# 8161930_003__3___2.net
KiCad netlist of a schematic drawn in Altium Designer
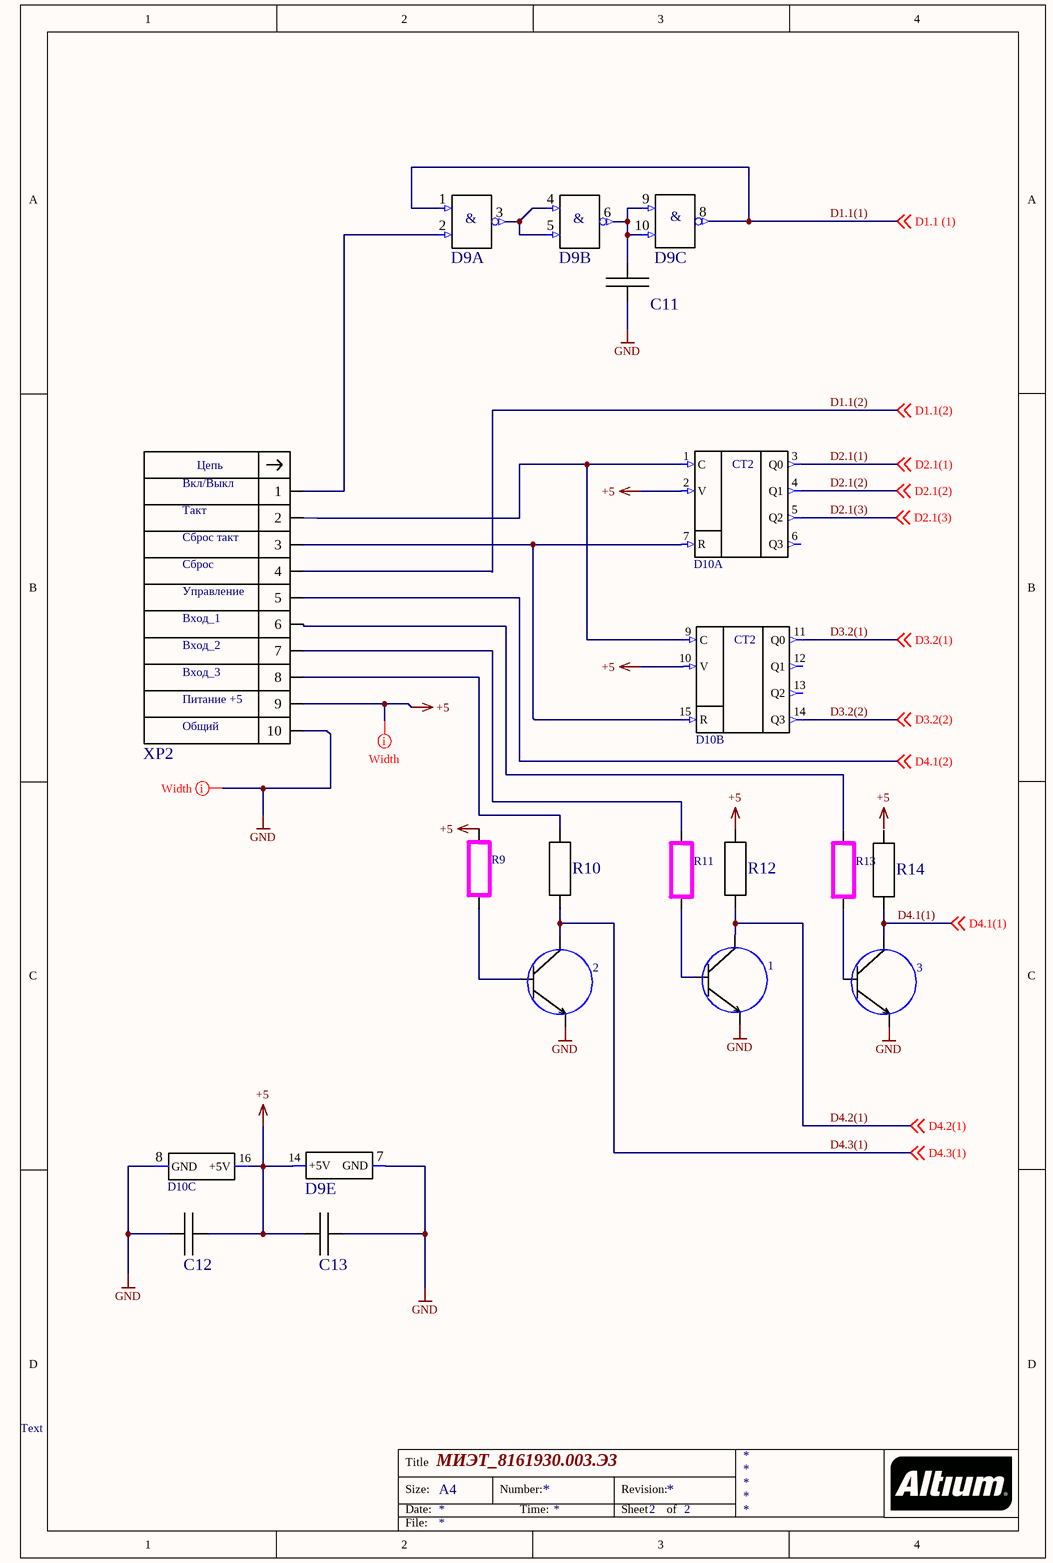
[diagram p0: МИЭТ_8161930_003_Э3_Лист_2.SchDoc]

(export (version "E")
  (design (tool "Eeschema 10.0.6"))
  (components
    (comp (ref "1")
      (value "Транзистор")
      (footprint "Schlib1:SOT89-150P340X160-3N")
      (description "Транзистор 2Т665А9 АЕЯР.432140.605 ТУ")
      (libsource (lib "Schlib1") (part "Транзистор"))
    )
    (comp (ref "2")
      (value "Транзистор")
      (footprint "Schlib1:SOT89-150P340X160-3N")
      (description "Транзистор 2Т665А9 АЕЯР.432140.605 ТУ")
      (libsource (lib "Schlib1") (part "Транзистор"))
    )
    (comp (ref "3")
      (value "Транзистор")
      (footprint "Schlib1:SOT89-150P340X160-3N")
      (description "Транзистор 2Т665А9 АЕЯР.432140.605 ТУ")
      (libsource (lib "Schlib1") (part "Транзистор"))
    )
    (comp (ref "C11")
      (value "~")
      (footprint "0805_N")
      (description "Чип конденсатор 0805 Н90 ряд Е6")
      (fields
        (field (name "MANUFACTURER") "ООО \"Кулон\"")
        (field (name "TOLERANCE") "+80%-20%")
        (field (name "CREATED_BY") "Желобаев")
      )
      (libsource (lib "Int_Library_for_Lessons") (part "К10-79_0805_Н90"))
    )
    (comp (ref "C12")
      (value "~")
      (footprint "0805_N")
      (description "Чип конденсатор 0805 Н90 ряд Е6")
      (fields
        (field (name "MANUFACTURER") "ООО \"Кулон\"")
        (field (name "TOLERANCE") "+80%-20%")
        (field (name "CREATED_BY") "Желобаев")
      )
      (libsource (lib "Int_Library_for_Lessons") (part "К10-79_0805_Н90"))
    )
    (comp (ref "C13")
      (value "~")
      (footprint "0805_N")
      (description "Чип конденсатор 0805 Н90 ряд Е6")
      (fields
        (field (name "MANUFACTURER") "ООО \"Кулон\"")
        (field (name "TOLERANCE") "+80%-20%")
        (field (name "CREATED_BY") "Желобаев")
      )
      (libsource (lib "Int_Library_for_Lessons") (part "К10-79_0805_Н90"))
    )
    (comp (ref "D9")
      (value "74AC00SC")
      (footprint "SO14-N")
      (description "4 элемента 2И-НЕ TTL SOIC-14")
      (fields (field (name "MANUFACTURER") "ON Semiconductor") (field (name "CREATED_BY") "Желобаев"))
      (libsource (lib "Int_Library_for_Lessons") (part "74AC00SC"))
    )
    (comp (ref "D10")
      (value "MC14520BDWG")
      (footprint "SOIC-16W-N")
      (description "Два двоичных счетчика")
      (fields (field (name "MANUFACTURER") "Motorola") (field (name "CREATED_BY") "Желобаев"))
      (libsource (lib "Int_Library_for_Lessons") (part "MC14520BDWG"))
    )
    (comp (ref "R9")
      (value "Резистор")
      (footprint "Schlib1:CAPC3225X06N")
      (description "Резистор Р1-12-0,1 4,7 кОм 5%-M-\"A\" АЛЯР.434110.005 ТУ")
      (libsource (lib "Schlib1") (part "Резистор"))
    )
    (comp (ref "R10")
      (value "0805")
      (footprint "RES_0805_2012_N")
      (description "Резистор от 0,75 Ом до 2 МОм")
      (fields
        (field (name "MANUFACTURER") "ОАО \"НПО \"Эркон\"")
        (field (name "TOLERANCE") "5%")
        (field (name "CREATED_BY") "Желобаев")
      )
      (libsource (lib "Int_Library_for_Lessons") (part "Р1-12-0,125-5%"))
    )
    (comp (ref "R11")
      (value "Резистор")
      (footprint "Schlib1:CAPC3225X06N")
      (description "Резистор Р1-12-0,1 4,7 кОм 5%-M-\"A\" АЛЯР.434110.005 ТУ")
      (libsource (lib "Schlib1") (part "Резистор"))
    )
    (comp (ref "R12")
      (value "0805")
      (footprint "RES_0805_2012_N")
      (description "Резистор от 0,75 Ом до 2 МОм")
      (fields
        (field (name "MANUFACTURER") "ОАО \"НПО \"Эркон\"")
        (field (name "TOLERANCE") "5%")
        (field (name "CREATED_BY") "Желобаев")
      )
      (libsource (lib "Int_Library_for_Lessons") (part "Р1-12-0,125-5%"))
    )
    (comp (ref "R13")
      (value "Резистор")
      (footprint "Schlib1:CAPC3225X06N")
      (description "Резистор Р1-12-0,1 4,7 кОм 5%-M-\"A\" АЛЯР.434110.005 ТУ")
      (libsource (lib "Schlib1") (part "Резистор"))
    )
    (comp (ref "R14")
      (value "0805")
      (footprint "RES_0805_2012_N")
      (description "Резистор от 0,75 Ом до 2 МОм")
      (fields
        (field (name "MANUFACTURER") "ОАО \"НПО \"Эркон\"")
        (field (name "TOLERANCE") "5%")
        (field (name "CREATED_BY") "Желобаев")
      )
      (libsource (lib "Int_Library_for_Lessons") (part "Р1-12-0,125-5%"))
    )
    (comp (ref "XP2")
      (value "TE_1-1634689-0")
      (footprint "BH-10R")
      (description "Вилка типа BH-10R угловая правая двухрядная 2х5х2.54")
      (fields (field (name "MANUFACTURER") "TE Connectivity") (field (name "CREATED_BY") "Желобаев"))
      (libsource (lib "Int_Library_for_Lessons") (part "TE_1-1634689-0"))
    )
  )
  (nets
    (net (code "1") (name "+5") (class "Default")
      (node (ref "C12") (pin "2") (pinfunction "2_2") (pintype "passive"))
      (node (ref "C13") (pin "1") (pinfunction "1_1") (pintype "passive"))
      (node (ref "D10") (pin "10") (pinfunction "V_10") (pintype "input"))
      (node (ref "D10") (pin "16") (pinfunction "+5V_16") (pintype "power_in"))
      (node (ref "D10") (pin "2") (pinfunction "V_2") (pintype "input"))
      (node (ref "D9") (pin "14") (pinfunction "+5V_14") (pintype "power_in"))
      (node (ref "R12") (pin "2") (pinfunction "2_2") (pintype "passive"))
      (node (ref "R9") (pin "2") (pinfunction "2_2") (pintype "passive"))
      (node (ref "XP2") (pin "9") (pinfunction "9_9") (pintype "passive"))
    )
    (net (code "2") (name "D1.1 (1)") (class "Default")
      (node (ref "D9") (pin "1") (pinfunction "In1_1") (pintype "input"))
      (node (ref "D9") (pin "8") (pinfunction "Out_8") (pintype "output"))
    )
    (net (code "3") (name "D1.1(2)") (class "Default")
      (node (ref "XP2") (pin "4") (pinfunction "4_4") (pintype "passive"))
    )
    (net (code "4") (name "D2.1(1)") (class "Default")
      (node (ref "D10") (pin "3") (pinfunction "Q0_3") (pintype "output"))
    )
    (net (code "5") (name "D2.1(2)") (class "Default")
      (node (ref "D10") (pin "4") (pinfunction "Q1_4") (pintype "output"))
    )
    (net (code "6") (name "D2.1(3)") (class "Default")
      (node (ref "D10") (pin "5") (pinfunction "Q2_5") (pintype "output"))
    )
    (net (code "7") (name "D3.2(1)") (class "Default")
      (node (ref "D10") (pin "11") (pinfunction "Q0_11") (pintype "output"))
    )
    (net (code "8") (name "D3.2(2)") (class "Default")
      (node (ref "D10") (pin "14") (pinfunction "Q3_14") (pintype "output"))
    )
    (net (code "9") (name "D4.1(1)") (class "Default")
      (node (ref "3") (pin "1") (pinfunction "1_1") (pintype "passive"))
      (node (ref "R14") (pin "2") (pinfunction "2_2") (pintype "passive"))
    )
    (net (code "10") (name "D4.1(2)") (class "Default")
      (node (ref "XP2") (pin "5") (pinfunction "5_5") (pintype "passive"))
    )
    (net (code "11") (name "D4.2(1)") (class "Default")
      (node (ref "1") (pin "1") (pinfunction "1_1") (pintype "passive"))
      (node (ref "R12") (pin "1") (pinfunction "1_1") (pintype "passive"))
    )
    (net (code "12") (name "D4.3(1)") (class "Default")
      (node (ref "2") (pin "1") (pinfunction "1_1") (pintype "passive"))
      (node (ref "R10") (pin "1") (pinfunction "1_1") (pintype "passive"))
    )
    (net (code "13") (name "GND") (class "Default")
      (node (ref "1") (pin "3") (pinfunction "3_3") (pintype "passive"))
      (node (ref "2") (pin "3") (pinfunction "3_3") (pintype "passive"))
      (node (ref "3") (pin "3") (pinfunction "3_3") (pintype "passive"))
      (node (ref "C11") (pin "1") (pinfunction "1_1") (pintype "passive"))
      (node (ref "C12") (pin "1") (pinfunction "1_1") (pintype "passive"))
      (node (ref "C13") (pin "2") (pinfunction "2_2") (pintype "passive"))
      (node (ref "D10") (pin "8") (pinfunction "GND_8") (pintype "power_in"))
      (node (ref "D9") (pin "7") (pinfunction "GND_7") (pintype "power_in"))
      (node (ref "XP2") (pin "10") (pinfunction "10_10") (pintype "passive"))
    )
    (net (code "14") (name "Net-(1-Pad2)") (class "Default")
      (node (ref "1") (pin "2") (pinfunction "2_2") (pintype "passive"))
      (node (ref "R11") (pin "1") (pinfunction "1_1") (pintype "passive"))
    )
    (net (code "15") (name "Net-(2-Pad2)") (class "Default")
      (node (ref "2") (pin "2") (pinfunction "2_2") (pintype "passive"))
      (node (ref "R9") (pin "1") (pinfunction "1_1") (pintype "passive"))
    )
    (net (code "16") (name "Net-(3-Pad2)") (class "Default")
      (node (ref "3") (pin "2") (pinfunction "2_2") (pintype "passive"))
      (node (ref "R13") (pin "1") (pinfunction "1_1") (pintype "passive"))
    )
    (net (code "17") (name "Net-(D9A-In2)") (class "Default")
      (node (ref "D9") (pin "2") (pinfunction "In2_2") (pintype "input"))
      (node (ref "XP2") (pin "1") (pinfunction "1_1") (pintype "passive"))
    )
    (net (code "18") (name "Net-(D9A-Out)") (class "Default")
      (node (ref "D9") (pin "3") (pinfunction "Out_3") (pintype "output"))
      (node (ref "D9") (pin "4") (pinfunction "In1_4") (pintype "input"))
      (node (ref "D9") (pin "5") (pinfunction "In2_5") (pintype "input"))
    )
    (net (code "19") (name "Net-(D9B-Out)") (class "Default")
      (node (ref "C11") (pin "2") (pinfunction "2_2") (pintype "passive"))
      (node (ref "D9") (pin "10") (pinfunction "In2_10") (pintype "input"))
      (node (ref "D9") (pin "6") (pinfunction "Out_6") (pintype "output"))
      (node (ref "D9") (pin "9") (pinfunction "In1_9") (pintype "input"))
    )
    (net (code "20") (name "Net-(D10A-C)") (class "Default")
      (node (ref "D10") (pin "1") (pinfunction "C_1") (pintype "input"))
      (node (ref "D10") (pin "9") (pinfunction "C_9") (pintype "input"))
      (node (ref "XP2") (pin "2") (pinfunction "2_2") (pintype "passive"))
    )
    (net (code "21") (name "Net-(D10A-R)") (class "Default")
      (node (ref "D10") (pin "15") (pinfunction "R_15") (pintype "input"))
      (node (ref "D10") (pin "7") (pinfunction "R_7") (pintype "input"))
      (node (ref "XP2") (pin "3") (pinfunction "3_3") (pintype "passive"))
    )
    (net (code "22") (name "Net-(R10-Pad2)") (class "Default")
      (node (ref "R10") (pin "2") (pinfunction "2_2") (pintype "passive"))
      (node (ref "XP2") (pin "8") (pinfunction "8_8") (pintype "passive"))
    )
    (net (code "23") (name "Net-(R11-Pad2)") (class "Default")
      (node (ref "R11") (pin "2") (pinfunction "2_2") (pintype "passive"))
      (node (ref "XP2") (pin "7") (pinfunction "7_7") (pintype "passive"))
    )
    (net (code "24") (name "Net-(R13-Pad2)") (class "Default")
      (node (ref "R13") (pin "2") (pinfunction "2_2") (pintype "passive"))
      (node (ref "XP2") (pin "6") (pinfunction "6_6") (pintype "passive"))
    )
    (net (code "25") (name "unconnected-(D10A-Q3-Pad6)") (class "Default")
      (node (ref "D10") (pin "6") (pinfunction "Q3_6") (pintype "output"))
    )
    (net (code "26") (name "unconnected-(D10B-Q1-Pad12)") (class "Default")
      (node (ref "D10") (pin "12") (pinfunction "Q1_12") (pintype "output"))
    )
    (net (code "27") (name "unconnected-(D10B-Q2-Pad13)") (class "Default")
      (node (ref "D10") (pin "13") (pinfunction "Q2_13") (pintype "output"))
    )
    (net (code "28") (name "unconnected-(R14-Pad1)") (class "Default")
      (node (ref "R14") (pin "1") (pinfunction "1_1") (pintype "passive"))
    )
  )
)
